# SSOP-16.net
KiCad netlist of a schematic drawn in EAGLE
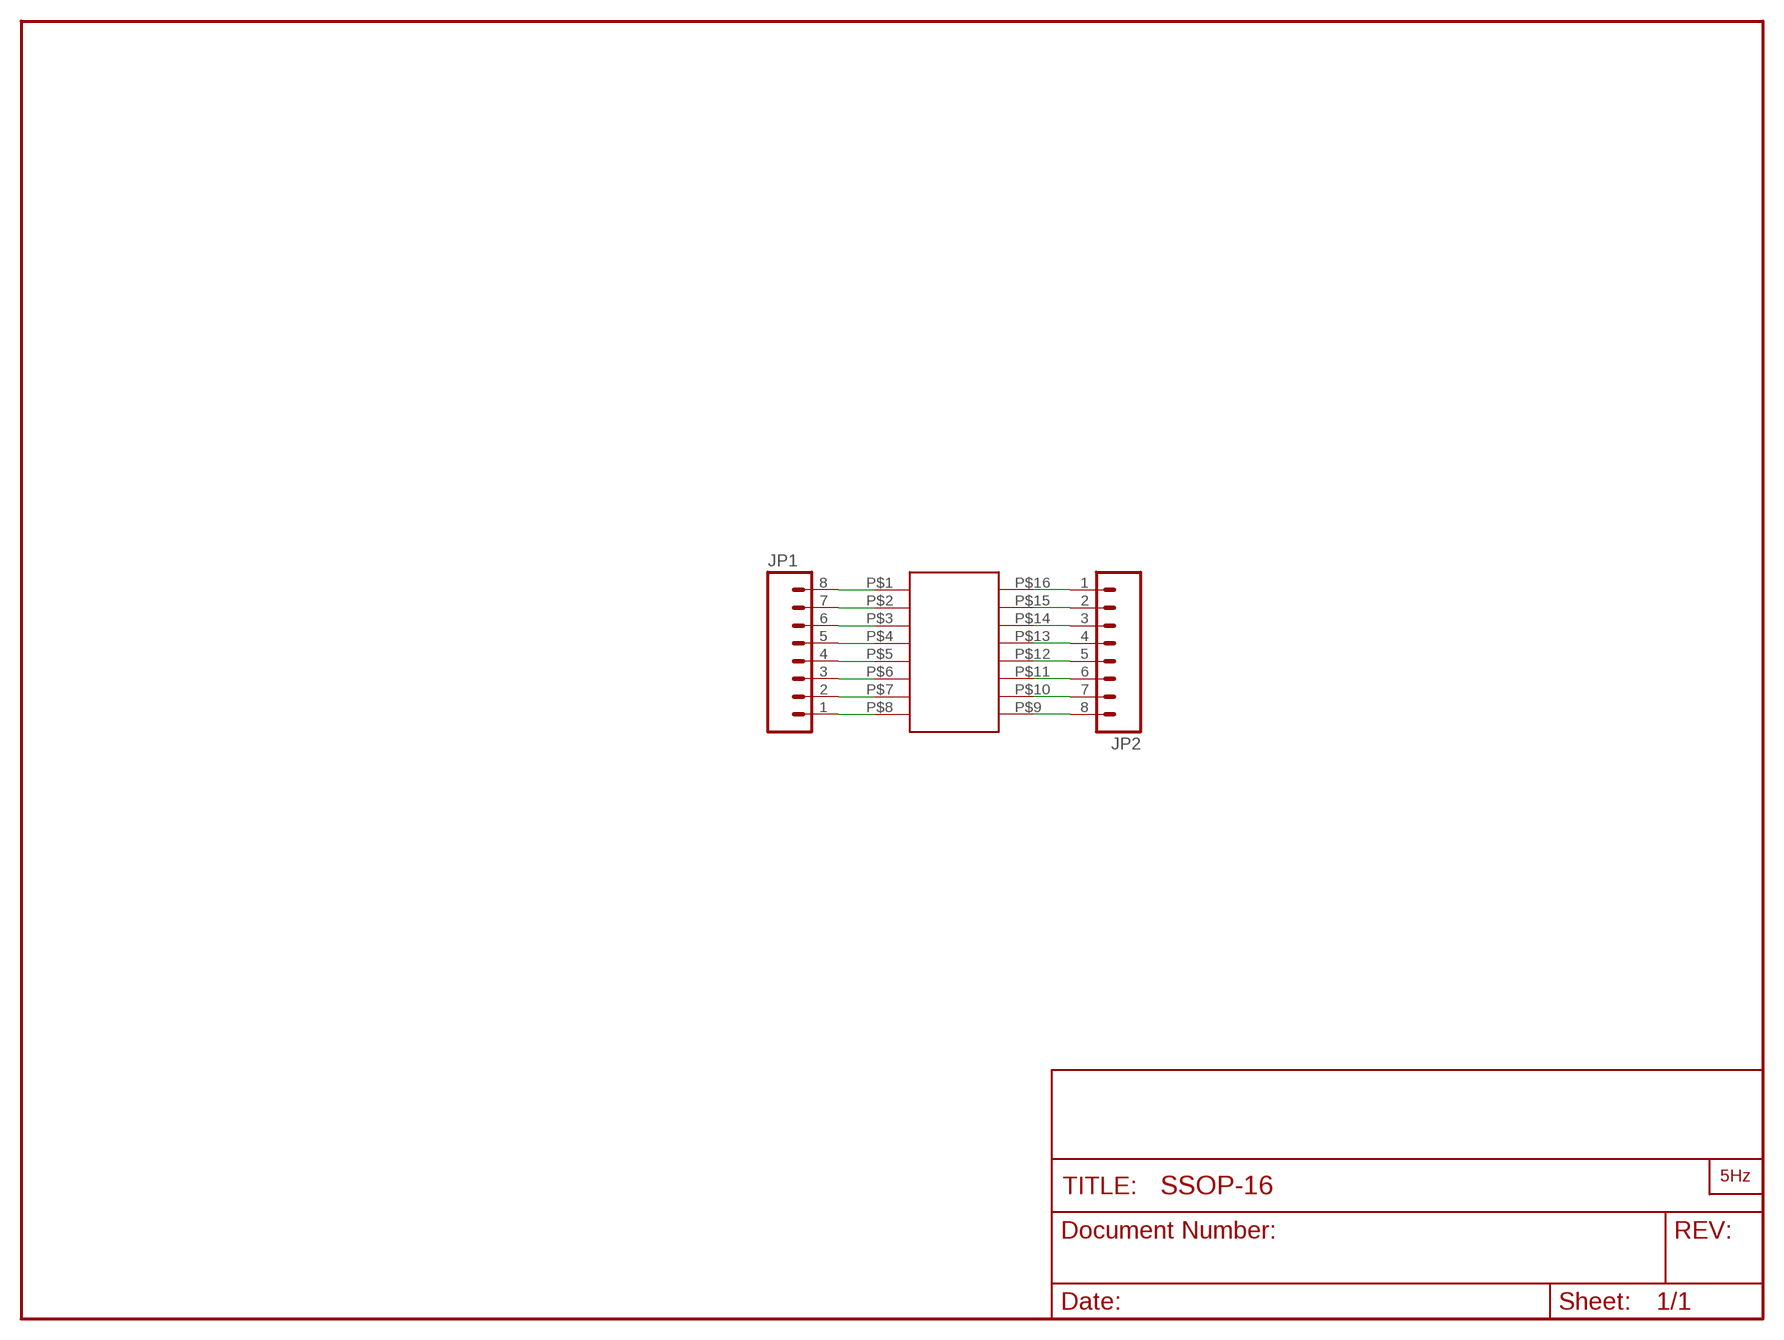
[diagram p0: schematic, sheet 1]

(export (version "E")
  (design (tool "Eeschema 10.0.6"))
  (components
    (comp (ref "JP1")
      (value "M081X08")
      (footprint "eagle-import:1X08")
      (libsource (lib "eagle-import") (part "M081X08"))
    )
    (comp (ref "JP2")
      (value "M081X08")
      (footprint "eagle-import:1X08")
      (libsource (lib "eagle-import") (part "M081X08"))
    )
    (comp (ref "U$1")
      (value "SSOP-16SSOP-16")
      (footprint "eagle-import:SSOP-16")
      (libsource (lib "eagle-import") (part "SSOP-16SSOP-16"))
    )
    (comp (ref "U$2")
      (value "LOGO2_SILK5MM")
      (footprint "eagle-import:LOGO2_5MM")
      (libsource (lib "eagle-import") (part "LOGO2_SILK5MM"))
    )
  )
  (nets
    (net (code "1") (name "Net-(JP1-Pad1)") (class "Default")
      (node (ref "JP1") (pin "1") (pinfunction "1_1") (pintype "passive"))
      (node (ref "U$1") (pin "P$8") (pinfunction "P$8_P$8") (pintype "bidirectional"))
    )
    (net (code "2") (name "Net-(JP1-Pad2)") (class "Default")
      (node (ref "JP1") (pin "2") (pinfunction "2_2") (pintype "passive"))
      (node (ref "U$1") (pin "P$7") (pinfunction "P$7_P$7") (pintype "bidirectional"))
    )
    (net (code "3") (name "Net-(JP1-Pad3)") (class "Default")
      (node (ref "JP1") (pin "3") (pinfunction "3_3") (pintype "passive"))
      (node (ref "U$1") (pin "P$6") (pinfunction "P$6_P$6") (pintype "bidirectional"))
    )
    (net (code "4") (name "Net-(JP1-Pad4)") (class "Default")
      (node (ref "JP1") (pin "4") (pinfunction "4_4") (pintype "passive"))
      (node (ref "U$1") (pin "P$5") (pinfunction "P$5_P$5") (pintype "bidirectional"))
    )
    (net (code "5") (name "Net-(JP1-Pad5)") (class "Default")
      (node (ref "JP1") (pin "5") (pinfunction "5_5") (pintype "passive"))
      (node (ref "U$1") (pin "P$4") (pinfunction "P$4_P$4") (pintype "bidirectional"))
    )
    (net (code "6") (name "Net-(JP1-Pad6)") (class "Default")
      (node (ref "JP1") (pin "6") (pinfunction "6_6") (pintype "passive"))
      (node (ref "U$1") (pin "P$3") (pinfunction "P$3_P$3") (pintype "bidirectional"))
    )
    (net (code "7") (name "Net-(JP1-Pad7)") (class "Default")
      (node (ref "JP1") (pin "7") (pinfunction "7_7") (pintype "passive"))
      (node (ref "U$1") (pin "P$2") (pinfunction "P$2_P$2") (pintype "bidirectional"))
    )
    (net (code "8") (name "Net-(JP1-Pad8)") (class "Default")
      (node (ref "JP1") (pin "8") (pinfunction "8_8") (pintype "passive"))
      (node (ref "U$1") (pin "P$1") (pinfunction "P$1_P$1") (pintype "bidirectional"))
    )
    (net (code "9") (name "Net-(JP2-Pad1)") (class "Default")
      (node (ref "JP2") (pin "1") (pinfunction "1_1") (pintype "passive"))
      (node (ref "U$1") (pin "P$16") (pinfunction "P$16_P$16") (pintype "bidirectional"))
    )
    (net (code "10") (name "Net-(JP2-Pad2)") (class "Default")
      (node (ref "JP2") (pin "2") (pinfunction "2_2") (pintype "passive"))
      (node (ref "U$1") (pin "P$15") (pinfunction "P$15_P$15") (pintype "bidirectional"))
    )
    (net (code "11") (name "Net-(JP2-Pad3)") (class "Default")
      (node (ref "JP2") (pin "3") (pinfunction "3_3") (pintype "passive"))
      (node (ref "U$1") (pin "P$14") (pinfunction "P$14_P$14") (pintype "bidirectional"))
    )
    (net (code "12") (name "Net-(JP2-Pad4)") (class "Default")
      (node (ref "JP2") (pin "4") (pinfunction "4_4") (pintype "passive"))
      (node (ref "U$1") (pin "P$13") (pinfunction "P$13_P$13") (pintype "bidirectional"))
    )
    (net (code "13") (name "Net-(JP2-Pad5)") (class "Default")
      (node (ref "JP2") (pin "5") (pinfunction "5_5") (pintype "passive"))
      (node (ref "U$1") (pin "P$12") (pinfunction "P$12_P$12") (pintype "bidirectional"))
    )
    (net (code "14") (name "Net-(JP2-Pad6)") (class "Default")
      (node (ref "JP2") (pin "6") (pinfunction "6_6") (pintype "passive"))
      (node (ref "U$1") (pin "P$11") (pinfunction "P$11_P$11") (pintype "bidirectional"))
    )
    (net (code "15") (name "Net-(JP2-Pad7)") (class "Default")
      (node (ref "JP2") (pin "7") (pinfunction "7_7") (pintype "passive"))
      (node (ref "U$1") (pin "P$10") (pinfunction "P$10_P$10") (pintype "bidirectional"))
    )
    (net (code "16") (name "Net-(JP2-Pad8)") (class "Default")
      (node (ref "JP2") (pin "8") (pinfunction "8_8") (pintype "passive"))
      (node (ref "U$1") (pin "P$9") (pinfunction "P$9_P$9") (pintype "bidirectional"))
    )
  )
)
